# Sheet1.net
KiCad netlist of a schematic drawn in Altium Designer
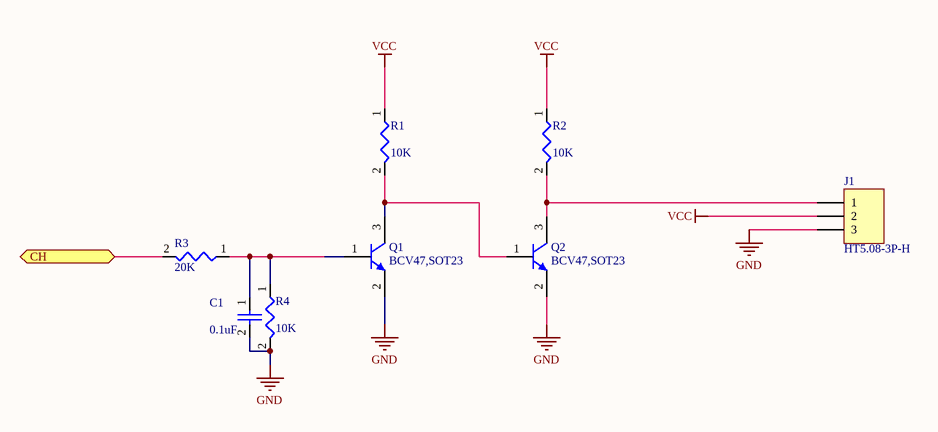
[diagram p0: Sheet1.SchDoc]

(export (version "E")
  (design (tool "Eeschema 10.0.6"))
  (components
    (comp (ref "C1")
      (value "0.1uF")
      (footprint "C0805")
      (description "CAP SMD CR X7R 50V 10% 0.1uF 0805 ROHS")
      (fields (field (name "MANUFACTURER") "YAGEO") (field (name "Comment") "CAP 0.1uF 50V 0805(2012)"))
      (libsource (lib "enlogic") (part "CAP"))
    )
    (comp (ref "J1")
      (value "HT5.08-3P-H")
      (footprint "HT5.08-3P-H")
      (description "Header, 3-Pin")
      (fields (field (name "PUBLISHER") "Altium Limited"))
      (libsource (lib "Miscellaneous Connectors") (part "Header 3"))
    )
    (comp (ref "Q1")
      (value "BCV47,SOT23")
      (footprint "INF-SOT23_L")
      (description "NPN Silicon Darlington Transistor, 60 V VCEO, 500 mA IC, SOT23, Reel, Green")
      (fields (field (name "PARTNUMBER") "BCV47") (field (name "MANUFACTURER") "Infineon"))
      (libsource (lib "Altium Content Vault") (part "CMP-1196-00014-1"))
    )
    (comp (ref "Q2")
      (value "BCV47,SOT23")
      (footprint "INF-SOT23_L")
      (description "NPN Silicon Darlington Transistor, 60 V VCEO, 500 mA IC, SOT23, Reel, Green")
      (fields (field (name "PARTNUMBER") "BCV47") (field (name "MANUFACTURER") "Infineon"))
      (libsource (lib "Altium Content Vault") (part "CMP-1196-00014-1"))
    )
    (comp (ref "R1")
      (value "10K")
      (footprint "R0805")
      (description "RES THICK_FILM SMD 10K ohm 5% 1/10W ROHS 0603")
      (fields (field (name "MANUFACTURER") "YAGEO") (field (name "Comment") "RES 10K 5% 0805(2012)"))
      (libsource (lib "Enlogic") (part "RES"))
    )
    (comp (ref "R2")
      (value "10K")
      (footprint "R0805")
      (description "RES THICK_FILM SMD 10K ohm 5% 1/10W ROHS 0603")
      (fields (field (name "MANUFACTURER") "YAGEO") (field (name "Comment") "RES 10K 5% 0805(2012)"))
      (libsource (lib "Enlogic") (part "RES"))
    )
    (comp (ref "R3")
      (value "20K")
      (footprint "R0805")
      (description "RES THICK_FILM SMD 100 OHM 5% 1/8W ROHS 0805")
      (fields (field (name "MANUFACTURER") "YAGEO") (field (name "Comment") "RES 20K 5% 0805(2012)"))
      (libsource (lib "enlogic") (part "RES"))
    )
    (comp (ref "R4")
      (value "10K")
      (footprint "R0805")
      (description "RES THICK_FILM SMD 10K ohm 5% 1/10W ROHS 0603")
      (fields (field (name "MANUFACTURER") "YAGEO") (field (name "Comment") "RES 10K 5% 0805(2012)"))
      (libsource (lib "Enlogic") (part "RES"))
    )
  )
  (nets
    (net (code "1") (name "/CH") (class "Default")
      (node (ref "R3") (pin "2") (pinfunction "2_2") (pintype "passive"))
    )
    (net (code "2") (name "GND") (class "Default")
      (node (ref "C1") (pin "2") (pinfunction "2_2") (pintype "passive"))
      (node (ref "J1") (pin "3") (pinfunction "3_3") (pintype "passive"))
      (node (ref "Q1") (pin "2") (pinfunction "E_2") (pintype "passive"))
      (node (ref "Q2") (pin "2") (pinfunction "E_2") (pintype "passive"))
      (node (ref "R4") (pin "2") (pinfunction "2_2") (pintype "passive"))
    )
    (net (code "3") (name "Net-(Q1-B)") (class "Default")
      (node (ref "C1") (pin "1") (pinfunction "1_1") (pintype "passive"))
      (node (ref "Q1") (pin "1") (pinfunction "B_1") (pintype "passive"))
      (node (ref "R3") (pin "1") (pinfunction "1_1") (pintype "passive"))
      (node (ref "R4") (pin "1") (pinfunction "1_1") (pintype "passive"))
    )
    (net (code "4") (name "Net-(Q1-C)") (class "Default")
      (node (ref "Q1") (pin "3") (pinfunction "C_3") (pintype "passive"))
      (node (ref "Q2") (pin "1") (pinfunction "B_1") (pintype "passive"))
      (node (ref "R1") (pin "2") (pinfunction "2_2") (pintype "passive"))
    )
    (net (code "5") (name "Net-(Q2-C)") (class "Default")
      (node (ref "J1") (pin "1") (pinfunction "1_1") (pintype "passive"))
      (node (ref "Q2") (pin "3") (pinfunction "C_3") (pintype "passive"))
      (node (ref "R2") (pin "2") (pinfunction "2_2") (pintype "passive"))
    )
    (net (code "6") (name "VCC") (class "Default")
      (node (ref "J1") (pin "2") (pinfunction "2_2") (pintype "passive"))
      (node (ref "R1") (pin "1") (pinfunction "1_1") (pintype "passive"))
      (node (ref "R2") (pin "1") (pinfunction "1_1") (pintype "passive"))
    )
  )
)
